# CiTEsch2.net
KiCad netlist of a schematic drawn in EAGLE
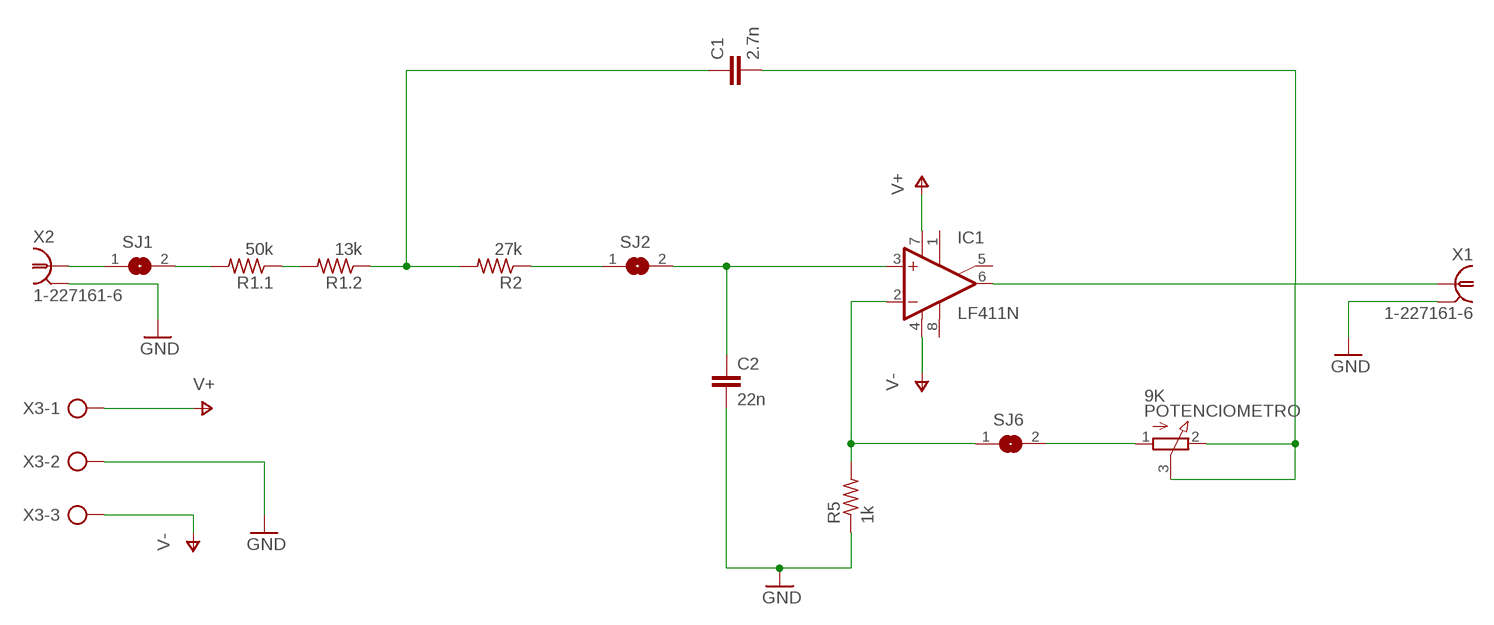
[diagram p0: schematic, sheet 1]

(export (version "E")
  (design (tool "Eeschema 10.0.6"))
  (components
    (comp (ref "9K")
      (value "POTENCIOMETRO")
      (footprint "eagle-import:TSM4YJ")
      (libsource (lib "eagle-import") (part "POTENCIOMETRO"))
    )
    (comp (ref "C1")
      (value "2.7n")
      (footprint "eagle-import:C050-025X075")
      (libsource (lib "eagle-import") (part "C-EU050-025X075"))
    )
    (comp (ref "C2")
      (value "22n")
      (footprint "eagle-import:C050-025X075")
      (libsource (lib "eagle-import") (part "C-EU050-025X075"))
    )
    (comp (ref "IC1")
      (value "LF411N")
      (footprint "eagle-import:DIL08")
      (libsource (lib "eagle-import") (part "LF411N"))
    )
    (comp (ref "R1.1")
      (value "50k")
      (footprint "eagle-import:0207_10")
      (libsource (lib "eagle-import") (part "R-US_0207/10"))
    )
    (comp (ref "R1.2")
      (value "13k")
      (footprint "eagle-import:0207_10")
      (libsource (lib "eagle-import") (part "R-US_0207/10"))
    )
    (comp (ref "R2")
      (value "27k")
      (footprint "eagle-import:0207_10")
      (libsource (lib "eagle-import") (part "R-US_0207/10"))
    )
    (comp (ref "R5")
      (value "1k")
      (footprint "eagle-import:0207_10")
      (libsource (lib "eagle-import") (part "R-US_0207/10"))
    )
    (comp (ref "SJ1")
      (value "SJW")
      (footprint "eagle-import:SJW")
      (libsource (lib "eagle-import") (part "SJW"))
    )
    (comp (ref "SJ2")
      (value "SJW")
      (footprint "eagle-import:SJW")
      (libsource (lib "eagle-import") (part "SJW"))
    )
    (comp (ref "SJ6")
      (value "SJW")
      (footprint "eagle-import:SJW")
      (libsource (lib "eagle-import") (part "SJW"))
    )
    (comp (ref "X1")
      (value "1-227161-6")
      (footprint "eagle-import:AMP_227161")
      (fields (field (name "MF") "TYCO ELECTRONICS"))
      (libsource (lib "eagle-import") (part "?2271611--6"))
    )
    (comp (ref "X2")
      (value "1-227161-6")
      (footprint "eagle-import:AMP_227161")
      (fields (field (name "MF") "TYCO ELECTRONICS"))
      (libsource (lib "eagle-import") (part "?2271611--6"))
    )
    (comp (ref "X3")
      (value "AK500/3")
      (footprint "eagle-import:AK500_3")
      (libsource (lib "eagle-import") (part "AK500/3"))
    )
  )
  (nets
    (net (code "1") (name "GND") (class "Default")
      (node (ref "C2") (pin "2") (pinfunction "2_2") (pintype "passive"))
      (node (ref "R5") (pin "1") (pinfunction "1_1") (pintype "passive"))
      (node (ref "X1") (pin "2") (pinfunction "2_2") (pintype "passive"))
      (node (ref "X2") (pin "2") (pinfunction "2_2") (pintype "passive"))
      (node (ref "X3") (pin "2") (pinfunction "KL_2") (pintype "passive"))
    )
    (net (code "2") (name "Net-(9K-A)") (class "Default")
      (node (ref "9K") (pin "1") (pinfunction "A_1") (pintype "passive"))
      (node (ref "SJ6") (pin "2") (pinfunction "2_2") (pintype "passive"))
    )
    (net (code "3") (name "Net-(9K-E)") (class "Default")
      (node (ref "9K") (pin "2") (pinfunction "E_2") (pintype "passive"))
      (node (ref "9K") (pin "3") (pinfunction "S_3") (pintype "passive"))
      (node (ref "C1") (pin "2") (pinfunction "2_2") (pintype "passive"))
      (node (ref "IC1") (pin "6") (pinfunction "OUT_6") (pintype "output"))
      (node (ref "X1") (pin "1") (pinfunction "1_1") (pintype "passive"))
    )
    (net (code "4") (name "Net-(C1-Pad1)") (class "Default")
      (node (ref "C1") (pin "1") (pinfunction "1_1") (pintype "passive"))
      (node (ref "R1.2") (pin "1") (pinfunction "1_1") (pintype "passive"))
      (node (ref "R2") (pin "2") (pinfunction "2_2") (pintype "passive"))
    )
    (net (code "5") (name "Net-(IC1-+IN)") (class "Default")
      (node (ref "C2") (pin "1") (pinfunction "1_1") (pintype "passive"))
      (node (ref "IC1") (pin "3") (pinfunction "+IN_3") (pintype "input"))
      (node (ref "SJ2") (pin "2") (pinfunction "2_2") (pintype "passive"))
    )
    (net (code "6") (name "Net-(IC1--IN)") (class "Default")
      (node (ref "IC1") (pin "2") (pinfunction "-IN_2") (pintype "input"))
      (node (ref "R5") (pin "2") (pinfunction "2_2") (pintype "passive"))
      (node (ref "SJ6") (pin "1") (pinfunction "1_1") (pintype "passive"))
    )
    (net (code "7") (name "Net-(R1.1-Pad1)") (class "Default")
      (node (ref "R1.1") (pin "1") (pinfunction "1_1") (pintype "passive"))
      (node (ref "R1.2") (pin "2") (pinfunction "2_2") (pintype "passive"))
    )
    (net (code "8") (name "Net-(R1.1-Pad2)") (class "Default")
      (node (ref "R1.1") (pin "2") (pinfunction "2_2") (pintype "passive"))
      (node (ref "SJ1") (pin "2") (pinfunction "2_2") (pintype "passive"))
    )
    (net (code "9") (name "Net-(R2-Pad1)") (class "Default")
      (node (ref "R2") (pin "1") (pinfunction "1_1") (pintype "passive"))
      (node (ref "SJ2") (pin "1") (pinfunction "1_1") (pintype "passive"))
    )
    (net (code "10") (name "Net-(SJ1-Pad1)") (class "Default")
      (node (ref "SJ1") (pin "1") (pinfunction "1_1") (pintype "passive"))
      (node (ref "X2") (pin "1") (pinfunction "1_1") (pintype "passive"))
    )
    (net (code "11") (name "V+") (class "Default")
      (node (ref "IC1") (pin "7") (pinfunction "V+_7") (pintype "power_in"))
      (node (ref "X3") (pin "1") (pinfunction "KL_1") (pintype "passive"))
    )
    (net (code "12") (name "V-") (class "Default")
      (node (ref "IC1") (pin "4") (pinfunction "V-_4") (pintype "power_in"))
      (node (ref "X3") (pin "3") (pinfunction "KL_3") (pintype "passive"))
    )
    (net (code "13") (name "unconnected-(IC1-ON1-Pad1)") (class "Default")
      (node (ref "IC1") (pin "1") (pinfunction "ON1_1") (pintype "passive"))
    )
    (net (code "14") (name "unconnected-(IC1-ON2-Pad5)") (class "Default")
      (node (ref "IC1") (pin "5") (pinfunction "ON2_5") (pintype "passive"))
    )
    (net (code "15") (name "unconnected-(IC1-OPT-Pad8)") (class "Default")
      (node (ref "IC1") (pin "8") (pinfunction "OPT_8") (pintype "passive"))
    )
  )
)
